# GPS_MAX-M8C-0-10.net
KiCad netlist of a schematic drawn in Altium Designer
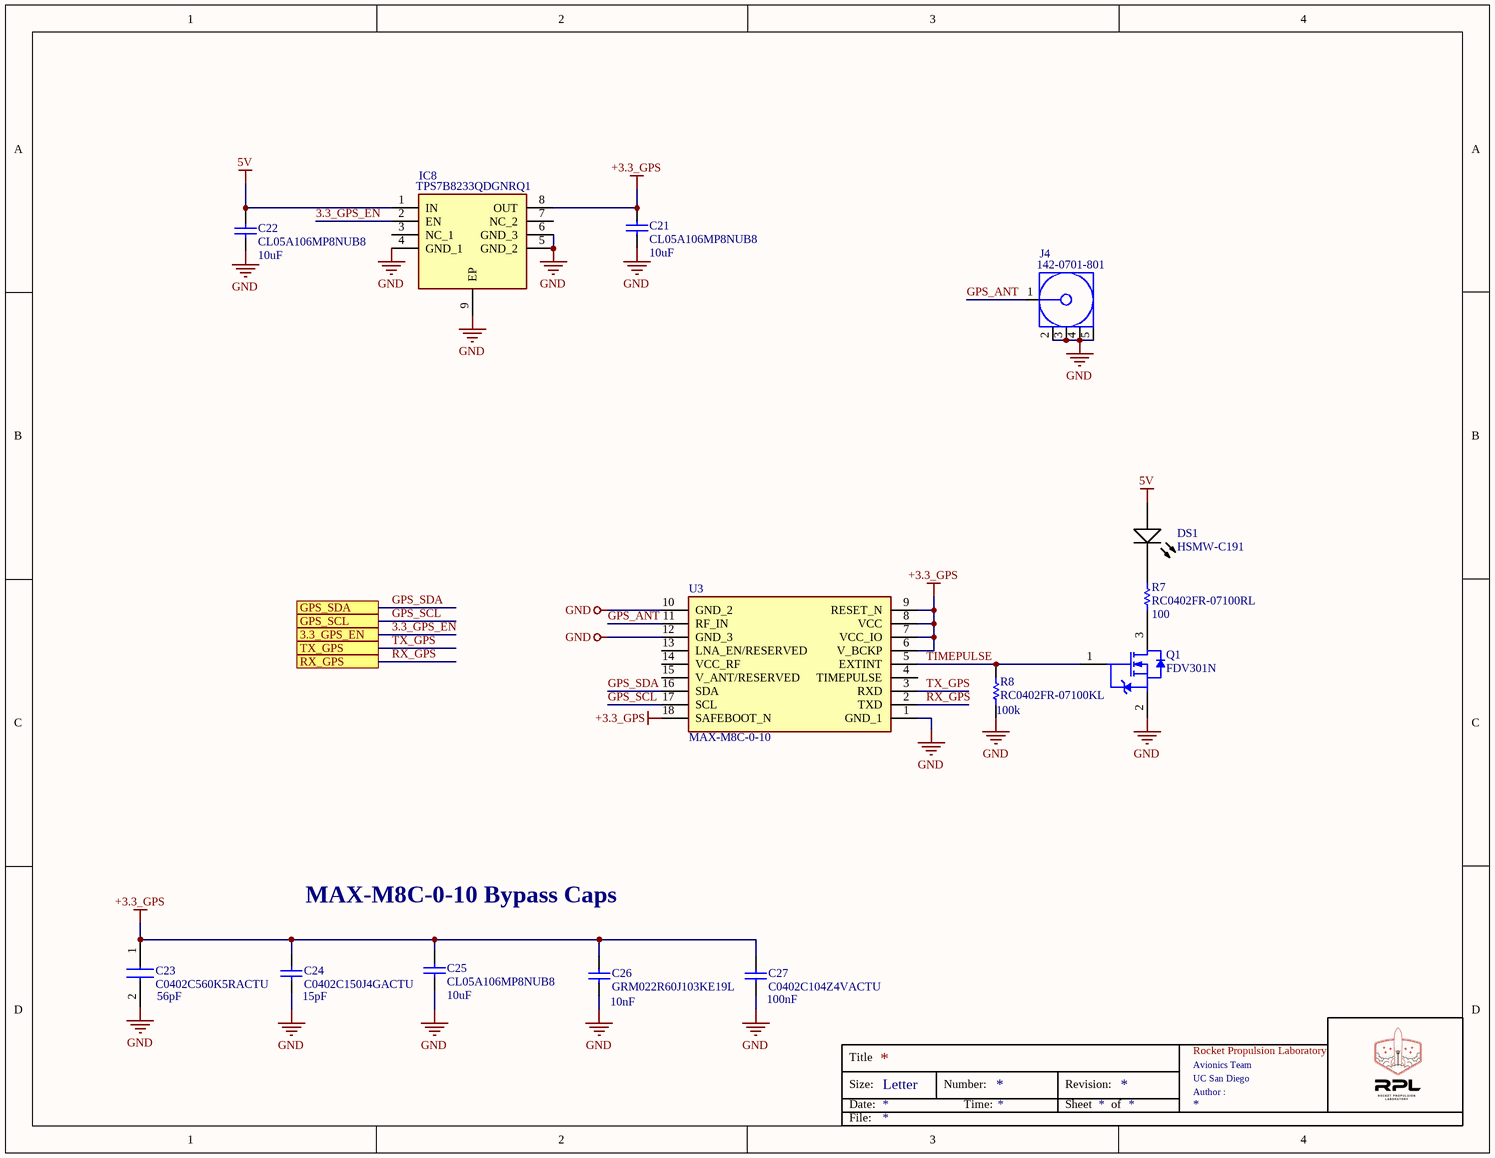
[diagram p0: GPS_MAX-M8C-0-10.SchDoc]

(export (version "E")
  (design (tool "Eeschema 10.0.6"))
  (components
    (comp (ref "C21")
      (value "CL05A106MP8NUB8")
      (footprint "0402")
      (description "Capacitor")
      (fields (field (name "ALTIUM_VALUE") "10uF") (field (name "PUBLISHER") "Altium Limited"))
      (libsource (lib "Miscellaneous Devices") (part "Cap"))
    )
    (comp (ref "C22")
      (value "CL05A106MP8NUB8")
      (footprint "0402")
      (description "Capacitor")
      (fields (field (name "ALTIUM_VALUE") "10uF") (field (name "PUBLISHER") "Altium Limited"))
      (libsource (lib "Miscellaneous Devices") (part "Cap"))
    )
    (comp (ref "C23")
      (value "C0402C560K5RACTU")
      (footprint "PcbLib1:CAPC1005X55N")
      (description "Capacitor")
      (fields (field (name "MOUSER PART NUMBER") "80-C0402C560K5RACTU") (field (name "ALTIUM_VALUE") "56pF"))
      (libsource (lib "*") (part "C0402C560K5RACTU"))
    )
    (comp (ref "C24")
      (value "C0402C150J4GACTU")
      (footprint "CAPC0402(1005)60_L")
      (description "CAP 15pF 16V ±5% 0402 (1005 Metric) Thickness 0.6mm SMD")
      (fields (field (name "ALTIUM_VALUE") "15pF") (field (name "TOLERANCE") "Â±5%"))
      (libsource (lib "Altium Content Vault") (part "CAP"))
    )
    (comp (ref "C25")
      (value "CL05A106MP8NUB8")
      (footprint "0402")
      (description "Capacitor")
      (fields (field (name "ALTIUM_VALUE") "10uF") (field (name "PUBLISHER") "Altium Limited"))
      (libsource (lib "Miscellaneous Devices") (part "Cap"))
    )
    (comp (ref "C26")
      (value "GRM022R60J103KE19L")
      (footprint "CAPC1005X55X25NL05T10")
      (fields (field (name "MANUFACTURER") "Murata") (field (name "ALTIUM_VALUE") "10nF"))
      (libsource (lib "Altium Content Vault") (part "CAP"))
    )
    (comp (ref "C27")
      (value "C0402C104Z4VACTU")
      (footprint "CAPC1005X55X30LL05T10")
      (fields (field (name "MANUFACTURER") "Kemet") (field (name "ALTIUM_VALUE") "100nF"))
      (libsource (lib "Altium Content Vault") (part "CAP"))
    )
    (comp (ref "DS1")
      (value "HSMW-C191")
      (footprint "AVAG-HSMW-C191_V")
      (description "LED Uni-Color White, 78 mW, 20 mA, -40 to 85 degC, 2-Pin SMD, RoHS, Tape and Reel")
      (libsource (lib "Altium Content Vault") (part "LED-WHITE-AK-2"))
    )
    (comp (ref "IC8")
      (value "TPS7B8233QDGNRQ1")
      (footprint "PcbLib1:SOP65P490X110-9N")
      (description "Integrated Circuit")
      (fields (field (name "MOUSER PART NUMBER") "595-TPS7B8233QDGNRQ1"))
      (libsource (lib "*") (part "TPS7B8233QDGNRQ1"))
    )
    (comp (ref "J4")
      (value "142-0701-801")
      (footprint "CINC-142-0701-801_V")
      (description "SMA End Launch Jack Receptacle, 50 Ohm, 0 to 18 GHz, -65 to 165 degC, 5-Pin SMD, RoHS, Bulk")
      (fields (field (name "MANUFACTURER") "EmersonConnectivitySolutions"))
      (libsource (lib "Altium Content Vault") (part "CN-S-4F-RF5"))
    )
    (comp (ref "Q1")
      (value "FDV301N")
      (footprint "FAIR-SOT23-3_V")
      (description "Digital FET, N-Channel, 0.35 W, 25 V, -55 to 150 degC, 3-Pin SOT23, RoHS, Tape and Reel")
      (fields (field (name "MANUFACTURER") "Fairchild"))
      (libsource (lib "Altium Content Vault") (part "NEMOS-GSD-3_D"))
    )
    (comp (ref "R7")
      (value "RC0402FR-07100RL")
      (footprint "RESC1005X40X25ML05T10")
      (fields (field (name "MANUFACTURER") "Yageo / Phycomp") (field (name "SPEC") "100"))
      (libsource (lib "Altium Content Vault") (part "RES"))
    )
    (comp (ref "R8")
      (value "RC0402FR-07100KL")
      (footprint "RESC1005X40X25NL05T10")
      (fields (field (name "MANUFACTURER") "Yageo / Phycomp") (field (name "SPEC") "100k"))
      (libsource (lib "Altium Content Vault") (part "RES"))
    )
    (comp (ref "U3")
      (value "MAX-M8C-0-10")
      (footprint "PcbLib1:MAX-M8")
      (description "Undefined or Miscellaneous")
      (libsource (lib "*") (part "MAX-M8C-0-10"))
    )
  )
  (nets
    (net (code "1") (name "+3.3_GPS") (class "Default")
      (node (ref "C21") (pin "2") (pinfunction "2_2") (pintype "passive"))
      (node (ref "C23") (pin "1") (pinfunction "1_1") (pintype "passive"))
      (node (ref "C24") (pin "1") (pinfunction "1_1") (pintype "passive"))
      (node (ref "C25") (pin "2") (pinfunction "2_2") (pintype "passive"))
      (node (ref "C26") (pin "2") (pinfunction "2_2") (pintype "passive"))
      (node (ref "C27") (pin "2") (pinfunction "2_2") (pintype "passive"))
      (node (ref "IC8") (pin "8") (pinfunction "OUT_8") (pintype "passive"))
      (node (ref "U3") (pin "18") (pinfunction "SAFEBOOT_N_18") (pintype "passive"))
      (node (ref "U3") (pin "6") (pinfunction "V_BCKP_6") (pintype "passive"))
      (node (ref "U3") (pin "7") (pinfunction "VCC_IO_7") (pintype "passive"))
      (node (ref "U3") (pin "8") (pinfunction "VCC_8") (pintype "passive"))
      (node (ref "U3") (pin "9") (pinfunction "RESET_N_9") (pintype "passive"))
    )
    (net (code "2") (name "/3.3_GPS_EN") (class "Default")
      (node (ref "IC8") (pin "2") (pinfunction "EN_2") (pintype "passive"))
    )
    (net (code "3") (name "/GPS_ANT") (class "Default")
      (node (ref "J4") (pin "1") (pinfunction "1_1") (pintype "passive"))
      (node (ref "U3") (pin "11") (pinfunction "RF_IN_11") (pintype "passive"))
    )
    (net (code "4") (name "/GPS_SCL") (class "Default")
      (node (ref "U3") (pin "17") (pinfunction "SCL_17") (pintype "passive"))
    )
    (net (code "5") (name "/GPS_SDA") (class "Default")
      (node (ref "U3") (pin "16") (pinfunction "SDA_16") (pintype "passive"))
    )
    (net (code "6") (name "/RX_GPS") (class "Default")
      (node (ref "U3") (pin "2") (pinfunction "TXD_2") (pintype "passive"))
    )
    (net (code "7") (name "/TIMEPULSE") (class "Default")
      (node (ref "Q1") (pin "1") (pinfunction "G_1") (pintype "passive"))
      (node (ref "R8") (pin "1") (pinfunction "1_1") (pintype "passive"))
      (node (ref "U3") (pin "5") (pinfunction "EXTINT_5") (pintype "passive"))
    )
    (net (code "8") (name "/TX_GPS") (class "Default")
      (node (ref "U3") (pin "3") (pinfunction "RXD_3") (pintype "passive"))
    )
    (net (code "9") (name "5V") (class "Default")
      (node (ref "C22") (pin "2") (pinfunction "2_2") (pintype "passive"))
      (node (ref "DS1") (pin "1") (pinfunction "A_1") (pintype "passive"))
      (node (ref "IC8") (pin "1") (pinfunction "IN_1") (pintype "passive"))
    )
    (net (code "10") (name "GND") (class "Default")
      (node (ref "C21") (pin "1") (pinfunction "1_1") (pintype "passive"))
      (node (ref "C22") (pin "1") (pinfunction "1_1") (pintype "passive"))
      (node (ref "C23") (pin "2") (pinfunction "2_2") (pintype "passive"))
      (node (ref "C24") (pin "2") (pinfunction "2_2") (pintype "passive"))
      (node (ref "C25") (pin "1") (pinfunction "1_1") (pintype "passive"))
      (node (ref "C26") (pin "1") (pinfunction "1_1") (pintype "passive"))
      (node (ref "C27") (pin "1") (pinfunction "1_1") (pintype "passive"))
      (node (ref "IC8") (pin "4") (pinfunction "GND_1_4") (pintype "passive"))
      (node (ref "IC8") (pin "5") (pinfunction "GND_2_5") (pintype "passive"))
      (node (ref "IC8") (pin "6") (pinfunction "GND_3_6") (pintype "passive"))
      (node (ref "IC8") (pin "9") (pinfunction "EP_9") (pintype "passive"))
      (node (ref "J4") (pin "2") (pinfunction "2_2") (pintype "passive"))
      (node (ref "J4") (pin "3") (pinfunction "3_3") (pintype "passive"))
      (node (ref "J4") (pin "4") (pinfunction "4_4") (pintype "passive"))
      (node (ref "J4") (pin "5") (pinfunction "5_5") (pintype "passive"))
      (node (ref "Q1") (pin "2") (pinfunction "S_2") (pintype "passive"))
      (node (ref "R8") (pin "2") (pinfunction "2_2") (pintype "passive"))
      (node (ref "U3") (pin "1") (pinfunction "GND_1_1") (pintype "passive"))
      (node (ref "U3") (pin "10") (pinfunction "GND_2_10") (pintype "passive"))
      (node (ref "U3") (pin "12") (pinfunction "GND_3_12") (pintype "passive"))
    )
    (net (code "11") (name "Net-(DS1-K)") (class "Default")
      (node (ref "DS1") (pin "2") (pinfunction "K_2") (pintype "passive"))
      (node (ref "R7") (pin "2") (pinfunction "2_2") (pintype "passive"))
    )
    (net (code "12") (name "Net-(Q1-D)") (class "Default")
      (node (ref "Q1") (pin "3") (pinfunction "D_3") (pintype "passive"))
      (node (ref "R7") (pin "1") (pinfunction "1_1") (pintype "passive"))
    )
    (net (code "13") (name "unconnected-(IC8-NC_1-Pad3)") (class "Default")
      (node (ref "IC8") (pin "3") (pinfunction "NC_1_3") (pintype "passive"))
    )
    (net (code "14") (name "unconnected-(IC8-NC_2-Pad7)") (class "Default")
      (node (ref "IC8") (pin "7") (pinfunction "NC_2_7") (pintype "passive"))
    )
    (net (code "15") (name "unconnected-(U3-LNA_EN{slash}RESERVED-Pad13)") (class "Default")
      (node (ref "U3") (pin "13") (pinfunction "LNA_EN/RESERVED_13") (pintype "passive"))
    )
    (net (code "16") (name "unconnected-(U3-TIMEPULSE-Pad4)") (class "Default")
      (node (ref "U3") (pin "4") (pinfunction "TIMEPULSE_4") (pintype "passive"))
    )
    (net (code "17") (name "unconnected-(U3-VCC_RF-Pad14)") (class "Default")
      (node (ref "U3") (pin "14") (pinfunction "VCC_RF_14") (pintype "passive"))
    )
    (net (code "18") (name "unconnected-(U3-V_ANT{slash}RESERVED-Pad15)") (class "Default")
      (node (ref "U3") (pin "15") (pinfunction "V_ANT/RESERVED_15") (pintype "passive"))
    )
  )
)
